# Sheet1.net
KiCad netlist of a schematic drawn in Altium Designer
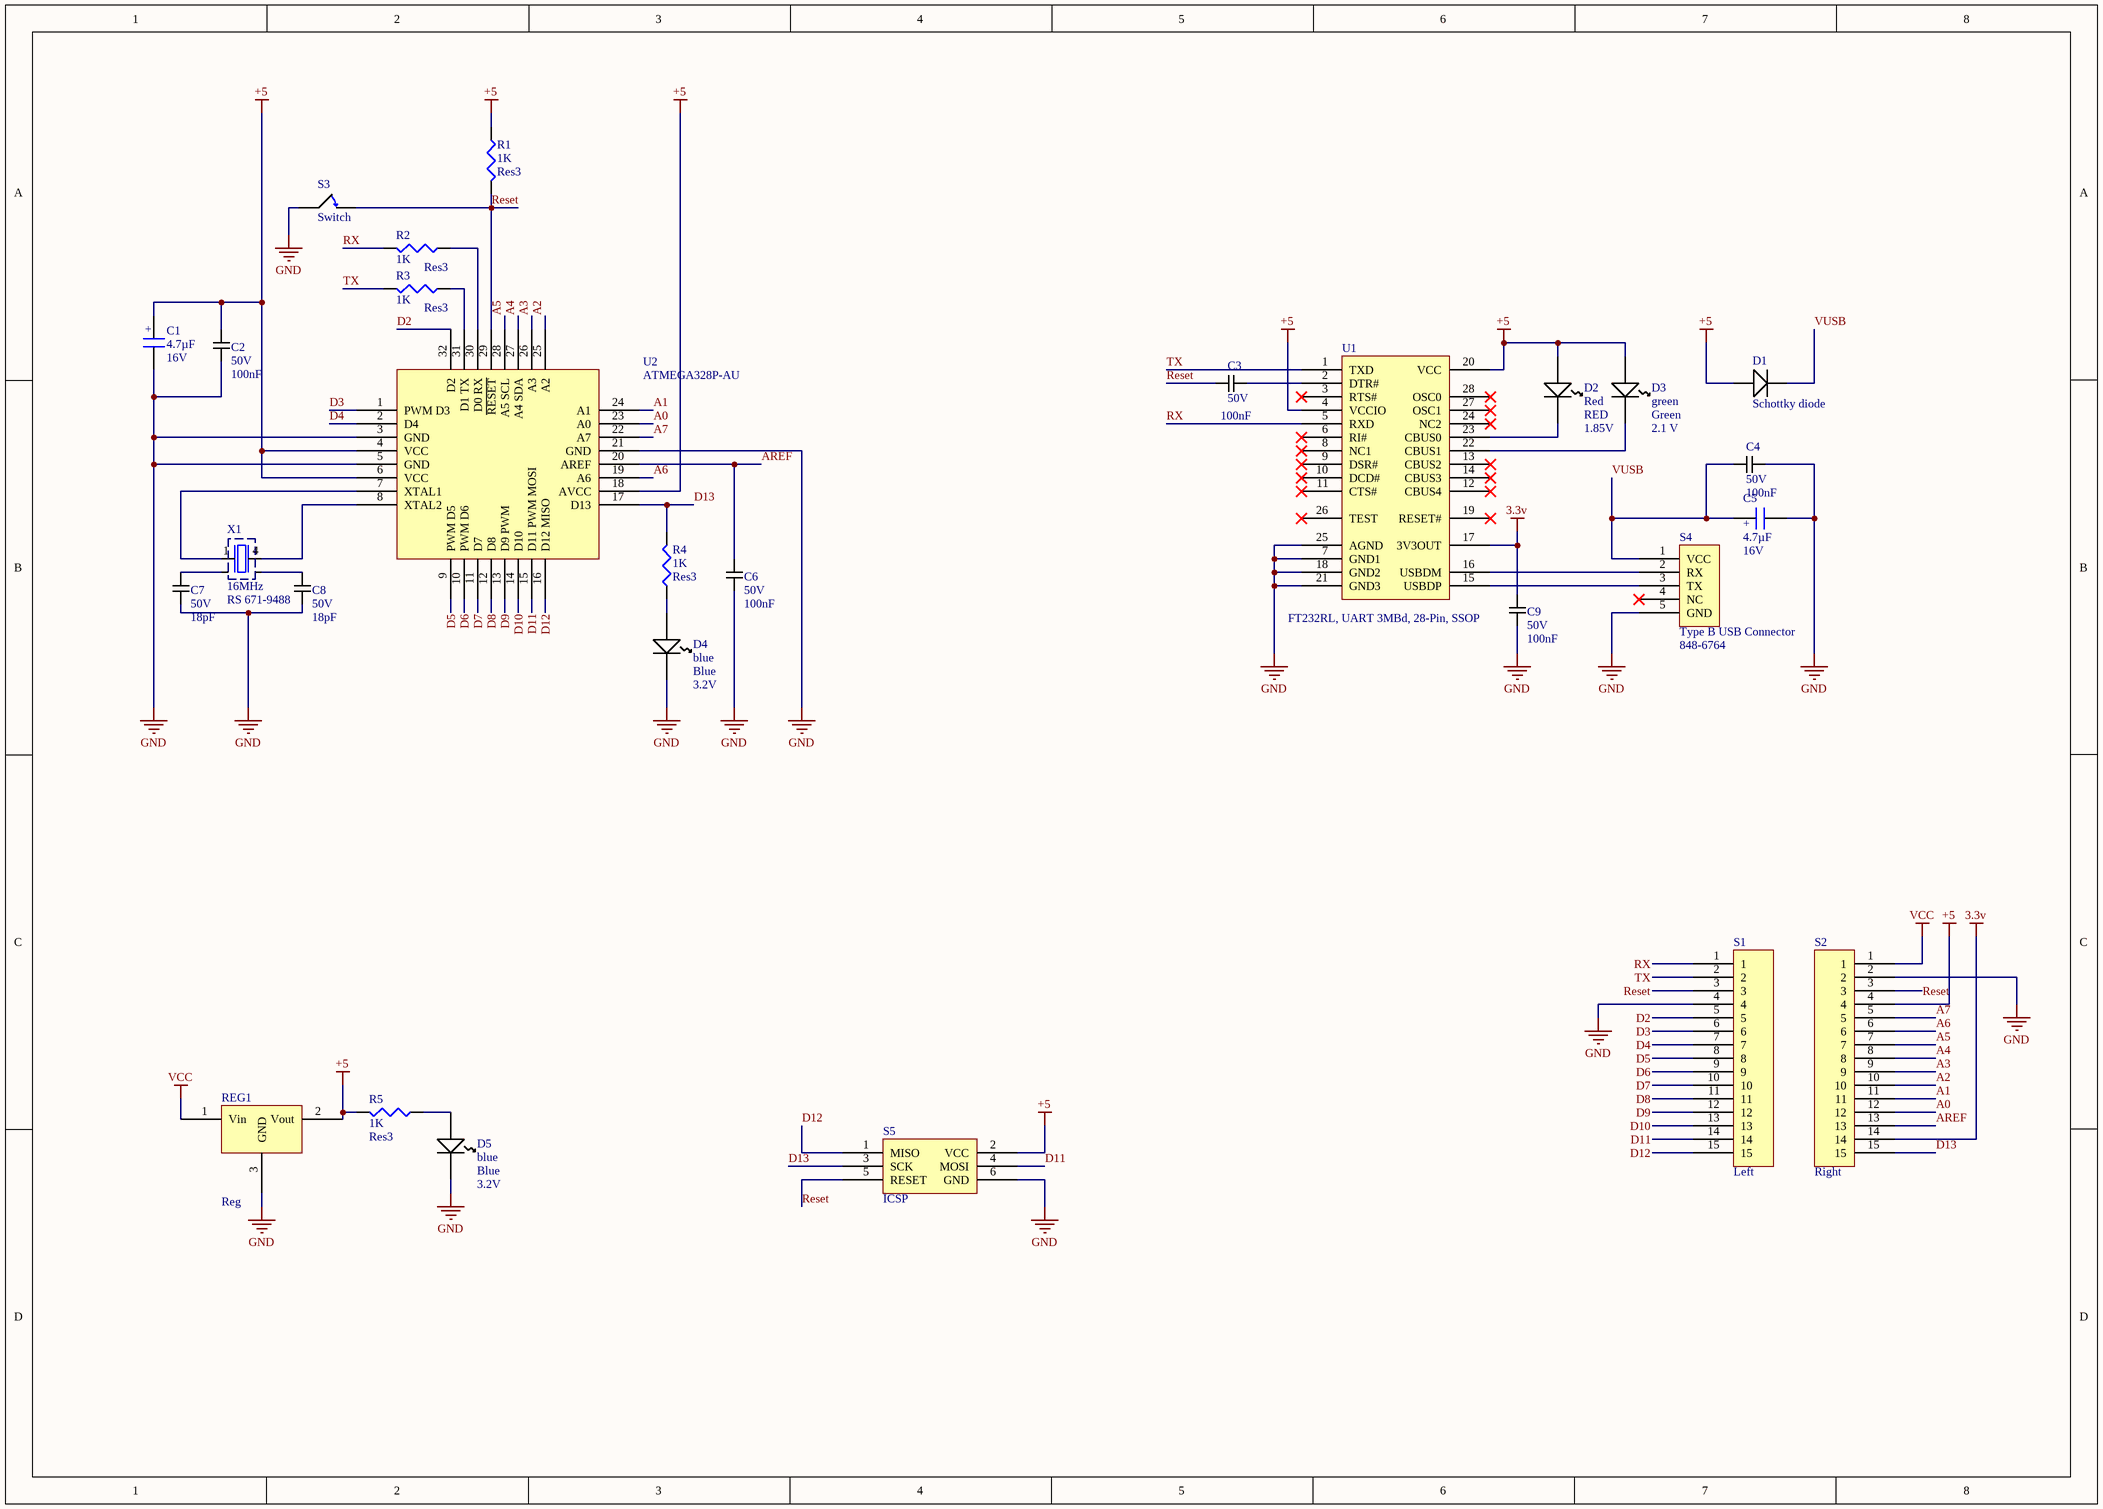
[diagram p0: Sheet1.SchDoc]

(export (version "E")
  (design (tool "Eeschema 10.0.6"))
  (components
    (comp (ref "C1")
      (value "4.7µF")
      (footprint "CASE A - 3216X18")
      (description "Capacitor,tantalum,SMT,16V,4.7uF,10%,A-case")
      (fields
        (field (name "TOLERANCE") "10%")
        (field (name "VOLTAGE") "16V")
        (field (name "Comment") "Capacitor SMT Tantalum")
        (field (name "PUBLISHER") "DPSS")
      )
      (libsource (lib "RS Components - Capacitors") (part "4.7µF Tant RS 496-3545"))
    )
    (comp (ref "C2")
      (value "100nF Ceramic Multilayer Capacitor_1")
      (footprint "CAPCP2012X09N")
      (description "AVX 0805 Standard 100nF Ceramic Multilayer Capacitor, 50 V dc X7R Dielectric ±10% SMD")
      (fields
        (field (name "MANUFACTURER") "AVX")
        (field (name "VOLTAGE") "50V")
        (field (name "CAPACITANCE") "100nF")
        (field (name "CREATOR") "Ritesh Kanjee")
      )
      (libsource (lib "RS Components - Capacitors") (part "100nF Ceramic Multilayer Capacitor_1"))
    )
    (comp (ref "C3")
      (value "100nF Ceramic Multilayer Capacitor_1")
      (footprint "CAPCP2012X09N")
      (description "AVX 0805 Standard 100nF Ceramic Multilayer Capacitor, 50 V dc X7R Dielectric ±10% SMD")
      (fields
        (field (name "MANUFACTURER") "AVX")
        (field (name "VOLTAGE") "50V")
        (field (name "CAPACITANCE") "100nF")
        (field (name "CREATOR") "Ritesh Kanjee")
      )
      (libsource (lib "RS Components - Capacitors") (part "100nF Ceramic Multilayer Capacitor_1"))
    )
    (comp (ref "C4")
      (value "100nF Ceramic Multilayer Capacitor_1")
      (footprint "CAPCP2012X09N")
      (description "AVX 0805 Standard 100nF Ceramic Multilayer Capacitor, 50 V dc X7R Dielectric ±10% SMD")
      (fields
        (field (name "MANUFACTURER") "AVX")
        (field (name "VOLTAGE") "50V")
        (field (name "CAPACITANCE") "100nF")
        (field (name "CREATOR") "Ritesh Kanjee")
      )
      (libsource (lib "RS Components - Capacitors") (part "100nF Ceramic Multilayer Capacitor_1"))
    )
    (comp (ref "C5")
      (value "4.7µF")
      (footprint "CASE A - 3216X18")
      (description "Capacitor,tantalum,SMT,16V,4.7uF,10%,A-case")
      (fields
        (field (name "TOLERANCE") "10%")
        (field (name "VOLTAGE") "16V")
        (field (name "Comment") "Capacitor SMT Tantalum")
        (field (name "PUBLISHER") "DPSS")
      )
      (libsource (lib "RS Components - Capacitors") (part "4.7µF Tant RS 496-3545"))
    )
    (comp (ref "C6")
      (value "100nF Ceramic Multilayer Capacitor_1")
      (footprint "CAPCP2012X09N")
      (description "AVX 0805 Standard 100nF Ceramic Multilayer Capacitor, 50 V dc X7R Dielectric ±10% SMD")
      (fields
        (field (name "MANUFACTURER") "AVX")
        (field (name "VOLTAGE") "50V")
        (field (name "CAPACITANCE") "100nF")
        (field (name "CREATOR") "Ritesh Kanjee")
      )
      (libsource (lib "RS Components - Capacitors") (part "100nF Ceramic Multilayer Capacitor_1"))
    )
    (comp (ref "C7")
      (value "C0805C180J5GACTU")
      (footprint "CAPCP2012X09N")
      (description "18pF Ceramic Multilayer Capacitor, 50 V dc C0G Dielectric ±5% SMD")
      (fields
        (field (name "MANUFACTURER") "Kemet")
        (field (name "VOLTAGE") "50V")
        (field (name "CAPACITANCE") "18pF")
        (field (name "CREATOR") "Ritesh Kanjee")
      )
      (libsource (lib "RS Components - Capacitors") (part "18pF Ceramic Multilayer Capacitor, 50 V dc C0G Dielectric ±5% SMD"))
    )
    (comp (ref "C8")
      (value "C0805C180J5GACTU")
      (footprint "CAPCP2012X09N")
      (description "18pF Ceramic Multilayer Capacitor, 50 V dc C0G Dielectric ±5% SMD")
      (fields
        (field (name "MANUFACTURER") "Kemet")
        (field (name "VOLTAGE") "50V")
        (field (name "CAPACITANCE") "18pF")
        (field (name "CREATOR") "Ritesh Kanjee")
      )
      (libsource (lib "RS Components - Capacitors") (part "18pF Ceramic Multilayer Capacitor, 50 V dc C0G Dielectric ±5% SMD"))
    )
    (comp (ref "C9")
      (value "100nF Ceramic Multilayer Capacitor_1")
      (footprint "CAPCP2012X09N")
      (description "AVX 0805 Standard 100nF Ceramic Multilayer Capacitor, 50 V dc X7R Dielectric ±10% SMD")
      (fields
        (field (name "MANUFACTURER") "AVX")
        (field (name "VOLTAGE") "50V")
        (field (name "CAPACITANCE") "100nF")
        (field (name "CREATOR") "Ritesh Kanjee")
      )
      (libsource (lib "RS Components - Capacitors") (part "100nF Ceramic Multilayer Capacitor_1"))
    )
    (comp (ref "D1")
      (value "Schottky diode")
      (footprint "DIOM1712X07N")
      (description "Panasonic DB2J20900L Schottky Diode, 0.5A, 20V, 2.4ns, 2-Pin SMini2 F5 B")
      (fields
        (field (name "MANUFACTURER") "Panasonic")
        (field (name "MANUFACTURER PART NO.") "DB2J20900L")
        (field (name "CREATED BY") "R Kanjee")
      )
      (libsource (lib "Panasonic Diodes") (part "Schottky Diode, 0.5A, 20V, 2.4ns, 2-Pin SMini2 F5 B"))
    )
    (comp (ref "D2")
      (value "Red")
      (footprint "LED1913X12NRED")
      (description "Kingbright Red LED, 100 mcd 120 ° 0805")
      (fields
        (field (name "MANUFACTURER") "KingBright")
        (field (name "MANUFACTURER PART NO.") "KP-2012SRC-PRV")
        (field (name "COLOR") "RED")
        (field (name "FORWARD VOLTAGE") "1.85V")
        (field (name "CREATOR") "Ritesh Kanjee")
      )
      (libsource (lib "KingBright LEDs") (part "Kingbright Red LED, 100 mcd 120 ° 0805"))
    )
    (comp (ref "D3")
      (value "green")
      (footprint "LED1913X12NGREEN")
      (description "Kingbright Green LED, 70 mcd 120 ° 0805")
      (fields
        (field (name "MANUFACTURER") "KingBright")
        (field (name "MANUFACTURER PART NO.") "KP-2012MGC")
        (field (name "COLOR") "Green")
        (field (name "FORWARD VOLTAGE") "2.1 V")
        (field (name "CREATOR") "Ritesh Kanjee")
      )
      (libsource (lib "KingBright LEDs") (part "Kingbright Green LED, 70 mcd 120 ° 0805"))
    )
    (comp (ref "D4")
      (value "blue")
      (footprint "LED1913X12NBLUE")
      (description "Kingbright Blue LED, 60 mcd 120 ° 0805")
      (fields
        (field (name "MANUFACTURER") "KingBright")
        (field (name "MANUFACTURER PART NO.") "KP-2012PBC-A")
        (field (name "COLOR") "Blue")
        (field (name "FORWARD VOLTAGE") "3.2V")
        (field (name "CREATOR") "Ritesh Kanjee")
      )
      (libsource (lib "KingBright LEDs") (part "Kingbright Blue LED, 60 mcd 120 ° 0805"))
    )
    (comp (ref "D5")
      (value "blue")
      (footprint "LED1913X12NBLUE")
      (description "Kingbright Blue LED, 60 mcd 120 ° 0805")
      (fields
        (field (name "MANUFACTURER") "KingBright")
        (field (name "MANUFACTURER PART NO.") "KP-2012PBC-A")
        (field (name "COLOR") "Blue")
        (field (name "FORWARD VOLTAGE") "3.2V")
        (field (name "CREATOR") "Ritesh Kanjee")
      )
      (libsource (lib "KingBright LEDs") (part "Kingbright Blue LED, 60 mcd 120 ° 0805"))
    )
    (comp (ref "R1")
      (value "Res3")
      (footprint "J1-0603")
      (description "Resistor")
      (fields (field (name "ALTIUM_VALUE") "1K") (field (name "PUBLISHER") "Altium Limited"))
      (libsource (lib "Miscellaneous+Devices") (part "Res3"))
    )
    (comp (ref "R2")
      (value "Res3")
      (footprint "J1-0603")
      (description "Resistor")
      (fields (field (name "ALTIUM_VALUE") "1K") (field (name "PUBLISHER") "Altium Limited"))
      (libsource (lib "Miscellaneous+Devices") (part "Res3"))
    )
    (comp (ref "R3")
      (value "Res3")
      (footprint "J1-0603")
      (description "Resistor")
      (fields (field (name "ALTIUM_VALUE") "1K") (field (name "PUBLISHER") "Altium Limited"))
      (libsource (lib "Miscellaneous+Devices") (part "Res3"))
    )
    (comp (ref "R4")
      (value "Res3")
      (footprint "J1-0603")
      (description "Resistor")
      (fields (field (name "ALTIUM_VALUE") "1K") (field (name "PUBLISHER") "Altium Limited"))
      (libsource (lib "Miscellaneous+Devices") (part "Res3"))
    )
    (comp (ref "R5")
      (value "Res3")
      (footprint "J1-0603")
      (description "Resistor")
      (fields (field (name "ALTIUM_VALUE") "1K") (field (name "PUBLISHER") "Altium Limited"))
      (libsource (lib "Miscellaneous+Devices") (part "Res3"))
    )
    (comp (ref "REG1")
      (value "Reg")
      (footprint "SOT230P700X180-4N")
      (description "LM1117MP-5.0/NOPB, Low Dropout Voltage Regulator, 1.5A, 5 V ±1%, 4-Pin SOT-223")
      (fields (field (name "MANUFACTURER") "Texas Instruments") (field (name "CREATED BY") "R Kanjee"))
      (libsource (lib "TI Low Dropout Voltage Regulator") (part "LM1117MP-5.0"))
    )
    (comp (ref "S1")
      (value "Left")
      (footprint "Header")
      (description "connector;str header;single row;.1 cont centers;.095 tail;gold or gtx;36 contact")
      (fields
        (field (name "MANUFACTURER") "FCI")
        (field (name "MANUFACTURER PART NO.") "68000-236HLF")
        (field (name "CREATED BY") "R Kanjee")
      )
      (libsource (lib "PCB Headers") (part "Single row; PCB headers"))
    )
    (comp (ref "S2")
      (value "Right")
      (footprint "Header")
      (description "connector;str header;single row;.1 cont centers;.095 tail;gold or gtx;36 contact")
      (fields
        (field (name "MANUFACTURER") "FCI")
        (field (name "MANUFACTURER PART NO.") "68000-236HLF")
        (field (name "CREATED BY") "R Kanjee")
      )
      (libsource (lib "") (part "Single row; PCB headers_1"))
    )
    (comp (ref "S3")
      (value "Switch")
      (footprint "Tactile Switch")
      (description "Tactile Switch SPST- NO 0.05A @24V")
      (fields
        (field (name "MANUFACTURER") "Omron")
        (field (name "MANUFACTURER PART NO.") "B3F1000")
        (field (name "CREATOR") "R Kanjee")
      )
      (libsource (lib "Omron Tactile Switches") (part "Tactile Switch SPST- NO 0.05A @24V"))
    )
    (comp (ref "S4")
      (value "Type B USB Connector")
      (footprint "MicroUSB")
      (description "NewMolex Right Angle SMT Female Type B Micro USB Connector, 30 V ac, 1.8A")
      (fields
        (field (name "MANUFACTURER") "Molex")
        (field (name "MANUFACTURER PART NO.") "105017-0001")
        (field (name "RS STOCK NO") "848-6764")
        (field (name "CREATOR") "R Kanjee")
      )
      (libsource (lib "Molex Connectors") (part "Micro USB Connector, 30 V ac, 1.8A"))
    )
    (comp (ref "S5")
      (value "ICSP")
      (footprint "ISP HEADER")
      (description "Programming Headers Dual Row")
      (fields
        (field (name "MANUFACTURER") "FCI")
        (field (name "MANUFACTURER PART NO.") "68000-236HLF")
        (field (name "CREATED BY") "R Kanjee")
      )
      (libsource (lib "PCB Headers") (part "Programming ISP, Programming Headers Dual Row"))
    )
    (comp (ref "U1")
      (value "FT232RL, UART 3MBd, 28-Pin, SSOP")
      (footprint "SOP65P780X200-28N")
      (description "FT232RL, Universal Asynchronous Receiver & Transmitter 3MBd, 28-Pin, SSOP")
      (fields
        (field (name "MANUFACTURER PART NO.") "FT232RL")
        (field (name "MANUFACTURER") "FTDI Chip")
        (field (name "CREATOR") "R Kanjee")
      )
      (libsource (lib "FTDI RS232toUSB") (part "FT232RL USB to UART, Universal Asynchronous Receiver & Transmitter 3MBd, 28-Pin, SSOP"))
    )
    (comp (ref "U2")
      (value "ATMEGA328P-AU")
      (footprint "TQFP80P900X900X120-32N")
      (description "ATMEGA328P-AU, 8 bit AVR Microcontroller 20MHz 1 kB, 32 kB Flash, 2 kB RAM, I2C 32-Pin TQFP")
      (fields (field (name "CREATED BY") "Ritesh Kanjee"))
      (libsource (lib "Atmel Microcontrollers") (part "ATMEGA328P-AU"))
    )
    (comp (ref "X1")
      (value "16MHz")
      (footprint "Aker S5C Crystal")
      (description "Aker S5C SMT Crystal")
      (fields
        (field (name "MANUFACTURER") "Aker")
        (field (name "MANUFACTURER PART #") "C5S-16.000-12-3030-X")
        (field (name "RS") "RS 671-9488")
        (field (name "CREATOR") "R Kanjee")
      )
      (libsource (lib "Aker Crystals") (part "Aker  C5S-16.000-12-3030-X"))
    )
  )
  (nets
    (net (code "1") (name "+5") (class "Default")
      (node (ref "C1") (pin "1") (pinfunction "1_1") (pintype "passive"))
      (node (ref "C2") (pin "2") (pinfunction "2_2") (pintype "passive"))
      (node (ref "D1") (pin "2") (pinfunction "2_2") (pintype "passive"))
      (node (ref "D2") (pin "1") (pinfunction "A_1") (pintype "passive"))
      (node (ref "D3") (pin "1") (pinfunction "A_1") (pintype "passive"))
      (node (ref "R1") (pin "1") (pinfunction "1_1") (pintype "passive"))
      (node (ref "R5") (pin "2") (pinfunction "2_2") (pintype "passive"))
      (node (ref "REG1") (pin "2") (pinfunction "Vout_2") (pintype "passive"))
      (node (ref "S2") (pin "4") (pinfunction "4_4") (pintype "passive"))
      (node (ref "S5") (pin "2") (pinfunction "VCC_2") (pintype "passive"))
      (node (ref "U1") (pin "20") (pinfunction "VCC_20") (pintype "passive"))
      (node (ref "U1") (pin "4") (pinfunction "VCCIO_4") (pintype "passive"))
      (node (ref "U2") (pin "18") (pinfunction "AVCC_18") (pintype "passive"))
      (node (ref "U2") (pin "4") (pinfunction "VCC_4") (pintype "passive"))
      (node (ref "U2") (pin "6") (pinfunction "VCC_6") (pintype "passive"))
    )
    (net (code "2") (name "/A0") (class "Default")
      (node (ref "S2") (pin "12") (pinfunction "12_12") (pintype "passive"))
      (node (ref "U2") (pin "23") (pinfunction "A0_23") (pintype "passive"))
    )
    (net (code "3") (name "/A1") (class "Default")
      (node (ref "S2") (pin "11") (pinfunction "11_11") (pintype "passive"))
      (node (ref "U2") (pin "24") (pinfunction "A1_24") (pintype "passive"))
    )
    (net (code "4") (name "/A2") (class "Default")
      (node (ref "S2") (pin "10") (pinfunction "10_10") (pintype "passive"))
      (node (ref "U2") (pin "25") (pinfunction "A2_25") (pintype "passive"))
    )
    (net (code "5") (name "/A3") (class "Default")
      (node (ref "S2") (pin "9") (pinfunction "9_9") (pintype "passive"))
      (node (ref "U2") (pin "26") (pinfunction "A3_26") (pintype "passive"))
    )
    (net (code "6") (name "/A4") (class "Default")
      (node (ref "S2") (pin "8") (pinfunction "8_8") (pintype "passive"))
      (node (ref "U2") (pin "27") (pinfunction "A4_SDA_27") (pintype "passive"))
    )
    (net (code "7") (name "/A5") (class "Default")
      (node (ref "S2") (pin "7") (pinfunction "7_7") (pintype "passive"))
      (node (ref "U2") (pin "28") (pinfunction "A5_SCL_28") (pintype "passive"))
    )
    (net (code "8") (name "/A6") (class "Default")
      (node (ref "S2") (pin "6") (pinfunction "6_6") (pintype "passive"))
      (node (ref "U2") (pin "19") (pinfunction "A6_19") (pintype "passive"))
    )
    (net (code "9") (name "/A7") (class "Default")
      (node (ref "S2") (pin "5") (pinfunction "5_5") (pintype "passive"))
      (node (ref "U2") (pin "22") (pinfunction "A7_22") (pintype "passive"))
    )
    (net (code "10") (name "/AREF") (class "Default")
      (node (ref "C6") (pin "2") (pinfunction "2_2") (pintype "passive"))
      (node (ref "S2") (pin "13") (pinfunction "13_13") (pintype "passive"))
      (node (ref "U2") (pin "20") (pinfunction "AREF_20") (pintype "passive"))
    )
    (net (code "11") (name "/D2") (class "Default")
      (node (ref "S1") (pin "5") (pinfunction "5_5") (pintype "passive"))
      (node (ref "U2") (pin "32") (pinfunction "D2_32") (pintype "passive"))
    )
    (net (code "12") (name "/D3") (class "Default")
      (node (ref "S1") (pin "6") (pinfunction "6_6") (pintype "passive"))
      (node (ref "U2") (pin "1") (pinfunction "PWM_D3_1") (pintype "passive"))
    )
    (net (code "13") (name "/D4") (class "Default")
      (node (ref "S1") (pin "7") (pinfunction "7_7") (pintype "passive"))
      (node (ref "U2") (pin "2") (pinfunction "D4_2") (pintype "passive"))
    )
    (net (code "14") (name "/D5") (class "Default")
      (node (ref "S1") (pin "8") (pinfunction "8_8") (pintype "passive"))
      (node (ref "U2") (pin "9") (pinfunction "PWM_D5_9") (pintype "passive"))
    )
    (net (code "15") (name "/D6") (class "Default")
      (node (ref "S1") (pin "9") (pinfunction "9_9") (pintype "passive"))
      (node (ref "U2") (pin "10") (pinfunction "PWM_D6_10") (pintype "passive"))
    )
    (net (code "16") (name "/D7") (class "Default")
      (node (ref "S1") (pin "10") (pinfunction "10_10") (pintype "passive"))
      (node (ref "U2") (pin "11") (pinfunction "D7_11") (pintype "passive"))
    )
    (net (code "17") (name "/D8") (class "Default")
      (node (ref "S1") (pin "11") (pinfunction "11_11") (pintype "passive"))
      (node (ref "U2") (pin "12") (pinfunction "D8_12") (pintype "passive"))
    )
    (net (code "18") (name "/D9") (class "Default")
      (node (ref "S1") (pin "12") (pinfunction "12_12") (pintype "passive"))
      (node (ref "U2") (pin "13") (pinfunction "D9_PWM_13") (pintype "passive"))
    )
    (net (code "19") (name "/D10") (class "Default")
      (node (ref "S1") (pin "13") (pinfunction "13_13") (pintype "passive"))
      (node (ref "U2") (pin "14") (pinfunction "D10_14") (pintype "passive"))
    )
    (net (code "20") (name "/D11") (class "Default")
      (node (ref "S1") (pin "14") (pinfunction "14_14") (pintype "passive"))
      (node (ref "S5") (pin "4") (pinfunction "MOSI_4") (pintype "passive"))
      (node (ref "U2") (pin "15") (pinfunction "D11_PWM_MOSI_15") (pintype "passive"))
    )
    (net (code "21") (name "/D12") (class "Default")
      (node (ref "S1") (pin "15") (pinfunction "15_15") (pintype "passive"))
      (node (ref "S5") (pin "1") (pinfunction "MISO_1") (pintype "passive"))
      (node (ref "U2") (pin "16") (pinfunction "D12_MISO_16") (pintype "passive"))
    )
    (net (code "22") (name "/D13") (class "Default")
      (node (ref "R4") (pin "2") (pinfunction "2_2") (pintype "passive"))
      (node (ref "S2") (pin "15") (pinfunction "15_15") (pintype "passive"))
      (node (ref "S5") (pin "3") (pinfunction "SCK_3") (pintype "passive"))
      (node (ref "U2") (pin "17") (pinfunction "D13_17") (pintype "passive"))
    )
    (net (code "23") (name "/RX") (class "Default")
      (node (ref "R2") (pin "2") (pinfunction "2_2") (pintype "passive"))
      (node (ref "S1") (pin "1") (pinfunction "1_1") (pintype "passive"))
      (node (ref "U1") (pin "5") (pinfunction "RXD_5") (pintype "passive"))
    )
    (net (code "24") (name "/Reset") (class "Default")
      (node (ref "C3") (pin "1") (pinfunction "1_1") (pintype "passive"))
      (node (ref "R1") (pin "2") (pinfunction "2_2") (pintype "passive"))
      (node (ref "S1") (pin "3") (pinfunction "3_3") (pintype "passive"))
      (node (ref "S2") (pin "3") (pinfunction "3_3") (pintype "passive"))
      (node (ref "S3") (pin "2") (pinfunction "2_2") (pintype "passive"))
      (node (ref "S5") (pin "5") (pinfunction "RESET_5") (pintype "passive"))
      (node (ref "U2") (pin "29") (pinfunction "~{RESET}_29") (pintype "passive"))
    )
    (net (code "25") (name "/TX") (class "Default")
      (node (ref "R3") (pin "2") (pinfunction "2_2") (pintype "passive"))
      (node (ref "S1") (pin "2") (pinfunction "2_2") (pintype "passive"))
      (node (ref "U1") (pin "1") (pinfunction "TXD_1") (pintype "passive"))
    )
    (net (code "26") (name "/VUSB") (class "Default")
      (node (ref "C4") (pin "1") (pinfunction "1_1") (pintype "passive"))
      (node (ref "C5") (pin "1") (pinfunction "1_1") (pintype "passive"))
      (node (ref "D1") (pin "1") (pinfunction "1_1") (pintype "passive"))
      (node (ref "S4") (pin "1") (pinfunction "VCC_1") (pintype "passive"))
    )
    (net (code "27") (name "3.3v") (class "Default")
      (node (ref "C9") (pin "1") (pinfunction "1_1") (pintype "passive"))
      (node (ref "S2") (pin "14") (pinfunction "14_14") (pintype "passive"))
      (node (ref "U1") (pin "17") (pinfunction "3V3OUT_17") (pintype "passive"))
    )
    (net (code "28") (name "GND") (class "Default")
      (node (ref "C1") (pin "2") (pinfunction "2_2") (pintype "passive"))
      (node (ref "C2") (pin "1") (pinfunction "1_1") (pintype "passive"))
      (node (ref "C4") (pin "2") (pinfunction "2_2") (pintype "passive"))
      (node (ref "C5") (pin "2") (pinfunction "2_2") (pintype "passive"))
      (node (ref "C6") (pin "1") (pinfunction "1_1") (pintype "passive"))
      (node (ref "C7") (pin "1") (pinfunction "1_1") (pintype "passive"))
      (node (ref "C8") (pin "1") (pinfunction "1_1") (pintype "passive"))
      (node (ref "C9") (pin "2") (pinfunction "2_2") (pintype "passive"))
      (node (ref "D4") (pin "2") (pinfunction "K_2") (pintype "passive"))
      (node (ref "D5") (pin "2") (pinfunction "K_2") (pintype "passive"))
      (node (ref "REG1") (pin "3") (pinfunction "GND_3") (pintype "passive"))
      (node (ref "S1") (pin "4") (pinfunction "4_4") (pintype "passive"))
      (node (ref "S2") (pin "2") (pinfunction "2_2") (pintype "passive"))
      (node (ref "S3") (pin "1") (pinfunction "1_1") (pintype "passive"))
      (node (ref "S4") (pin "5") (pinfunction "GND_5") (pintype "passive"))
      (node (ref "S5") (pin "6") (pinfunction "GND_6") (pintype "passive"))
      (node (ref "U1") (pin "18") (pinfunction "GND2_18") (pintype "passive"))
      (node (ref "U1") (pin "21") (pinfunction "GND3_21") (pintype "passive"))
      (node (ref "U1") (pin "25") (pinfunction "AGND_25") (pintype "passive"))
      (node (ref "U1") (pin "7") (pinfunction "GND1_7") (pintype "passive"))
      (node (ref "U2") (pin "21") (pinfunction "GND_21") (pintype "passive"))
      (node (ref "U2") (pin "3") (pinfunction "GND_3") (pintype "passive"))
      (node (ref "U2") (pin "5") (pinfunction "GND_5") (pintype "passive"))
    )
    (net (code "29") (name "Net-(C7-Pad2)") (class "Default")
      (node (ref "C7") (pin "2") (pinfunction "2_2") (pintype "passive"))
      (node (ref "X1") (pin "3") (pinfunction "Gnd_3") (pintype "power_in"))
    )
    (net (code "30") (name "Net-(C8-Pad2)") (class "Default")
      (node (ref "C8") (pin "2") (pinfunction "2_2") (pintype "passive"))
      (node (ref "X1") (pin "2") (pinfunction "Gnd_2") (pintype "power_in"))
    )
    (net (code "31") (name "Net-(D2-K)") (class "Default")
      (node (ref "D2") (pin "2") (pinfunction "K_2") (pintype "passive"))
      (node (ref "U1") (pin "23") (pinfunction "CBUS0_23") (pintype "passive"))
    )
    (net (code "32") (name "Net-(D3-K)") (class "Default")
      (node (ref "D3") (pin "2") (pinfunction "K_2") (pintype "passive"))
      (node (ref "U1") (pin "22") (pinfunction "CBUS1_22") (pintype "passive"))
    )
    (net (code "33") (name "Net-(D4-A)") (class "Default")
      (node (ref "D4") (pin "1") (pinfunction "A_1") (pintype "passive"))
      (node (ref "R4") (pin "1") (pinfunction "1_1") (pintype "passive"))
    )
    (net (code "34") (name "Net-(D5-A)") (class "Default")
      (node (ref "D5") (pin "1") (pinfunction "A_1") (pintype "passive"))
      (node (ref "R5") (pin "1") (pinfunction "1_1") (pintype "passive"))
    )
    (net (code "35") (name "Net-(S4-RX)") (class "Default")
      (node (ref "S4") (pin "2") (pinfunction "RX_2") (pintype "passive"))
      (node (ref "U1") (pin "16") (pinfunction "USBDM_16") (pintype "passive"))
    )
    (net (code "36") (name "Net-(S4-TX)") (class "Default")
      (node (ref "S4") (pin "3") (pinfunction "TX_3") (pintype "passive"))
      (node (ref "U1") (pin "15") (pinfunction "USBDP_15") (pintype "passive"))
    )
    (net (code "37") (name "Net-(U1-DTR#)") (class "Default")
      (node (ref "C3") (pin "2") (pinfunction "2_2") (pintype "passive"))
      (node (ref "U1") (pin "2") (pinfunction "DTR#_2") (pintype "passive"))
    )
    (net (code "38") (name "Net-(U2-D0_RX)") (class "Default")
      (node (ref "R2") (pin "1") (pinfunction "1_1") (pintype "passive"))
      (node (ref "U2") (pin "30") (pinfunction "D0_RX_30") (pintype "passive"))
    )
    (net (code "39") (name "Net-(U2-D1_TX)") (class "Default")
      (node (ref "R3") (pin "1") (pinfunction "1_1") (pintype "passive"))
      (node (ref "U2") (pin "31") (pinfunction "D1_TX_31") (pintype "passive"))
    )
    (net (code "40") (name "Net-(U2-XTAL1)") (class "Default")
      (node (ref "U2") (pin "7") (pinfunction "XTAL1_7") (pintype "passive"))
      (node (ref "X1") (pin "1") (pinfunction "1_1") (pintype "passive"))
    )
    (net (code "41") (name "Net-(U2-XTAL2)") (class "Default")
      (node (ref "U2") (pin "8") (pinfunction "XTAL2_8") (pintype "passive"))
      (node (ref "X1") (pin "4") (pinfunction "4_4") (pintype "passive"))
    )
    (net (code "42") (name "VCC") (class "Default")
      (node (ref "REG1") (pin "1") (pinfunction "Vin_1") (pintype "passive"))
      (node (ref "S2") (pin "1") (pinfunction "1_1") (pintype "passive"))
    )
    (net (code "43") (name "unconnected-(S4-NC-Pad4)") (class "Default")
      (node (ref "S4") (pin "4") (pinfunction "NC_4") (pintype "passive+no_connect"))
    )
    (net (code "44") (name "unconnected-(U1-CBUS2-Pad13)") (class "Default")
      (node (ref "U1") (pin "13") (pinfunction "CBUS2_13") (pintype "passive+no_connect"))
    )
    (net (code "45") (name "unconnected-(U1-CBUS3-Pad14)") (class "Default")
      (node (ref "U1") (pin "14") (pinfunction "CBUS3_14") (pintype "passive+no_connect"))
    )
    (net (code "46") (name "unconnected-(U1-CBUS4-Pad12)") (class "Default")
      (node (ref "U1") (pin "12") (pinfunction "CBUS4_12") (pintype "passive+no_connect"))
    )
    (net (code "47") (name "unconnected-(U1-CTS#-Pad11)") (class "Default")
      (node (ref "U1") (pin "11") (pinfunction "CTS#_11") (pintype "passive+no_connect"))
    )
    (net (code "48") (name "unconnected-(U1-DCD#-Pad10)") (class "Default")
      (node (ref "U1") (pin "10") (pinfunction "DCD#_10") (pintype "passive+no_connect"))
    )
    (net (code "49") (name "unconnected-(U1-DSR#-Pad9)") (class "Default")
      (node (ref "U1") (pin "9") (pinfunction "DSR#_9") (pintype "passive+no_connect"))
    )
    (net (code "50") (name "unconnected-(U1-NC1-Pad8)") (class "Default")
      (node (ref "U1") (pin "8") (pinfunction "NC1_8") (pintype "passive+no_connect"))
    )
    (net (code "51") (name "unconnected-(U1-NC2-Pad24)") (class "Default")
      (node (ref "U1") (pin "24") (pinfunction "NC2_24") (pintype "passive+no_connect"))
    )
    (net (code "52") (name "unconnected-(U1-OSC0-Pad28)") (class "Default")
      (node (ref "U1") (pin "28") (pinfunction "OSC0_28") (pintype "passive+no_connect"))
    )
    (net (code "53") (name "unconnected-(U1-OSC1-Pad27)") (class "Default")
      (node (ref "U1") (pin "27") (pinfunction "OSC1_27") (pintype "passive+no_connect"))
    )
    (net (code "54") (name "unconnected-(U1-RESET#-Pad19)") (class "Default")
      (node (ref "U1") (pin "19") (pinfunction "RESET#_19") (pintype "passive+no_connect"))
    )
    (net (code "55") (name "unconnected-(U1-RI#-Pad6)") (class "Default")
      (node (ref "U1") (pin "6") (pinfunction "RI#_6") (pintype "passive+no_connect"))
    )
    (net (code "56") (name "unconnected-(U1-RTS#-Pad3)") (class "Default")
      (node (ref "U1") (pin "3") (pinfunction "RTS#_3") (pintype "passive+no_connect"))
    )
    (net (code "57") (name "unconnected-(U1-TEST-Pad26)") (class "Default")
      (node (ref "U1") (pin "26") (pinfunction "TEST_26") (pintype "passive+no_connect"))
    )
  )
)
